# design.net
KiCad netlist of a schematic drawn in Altium Designer
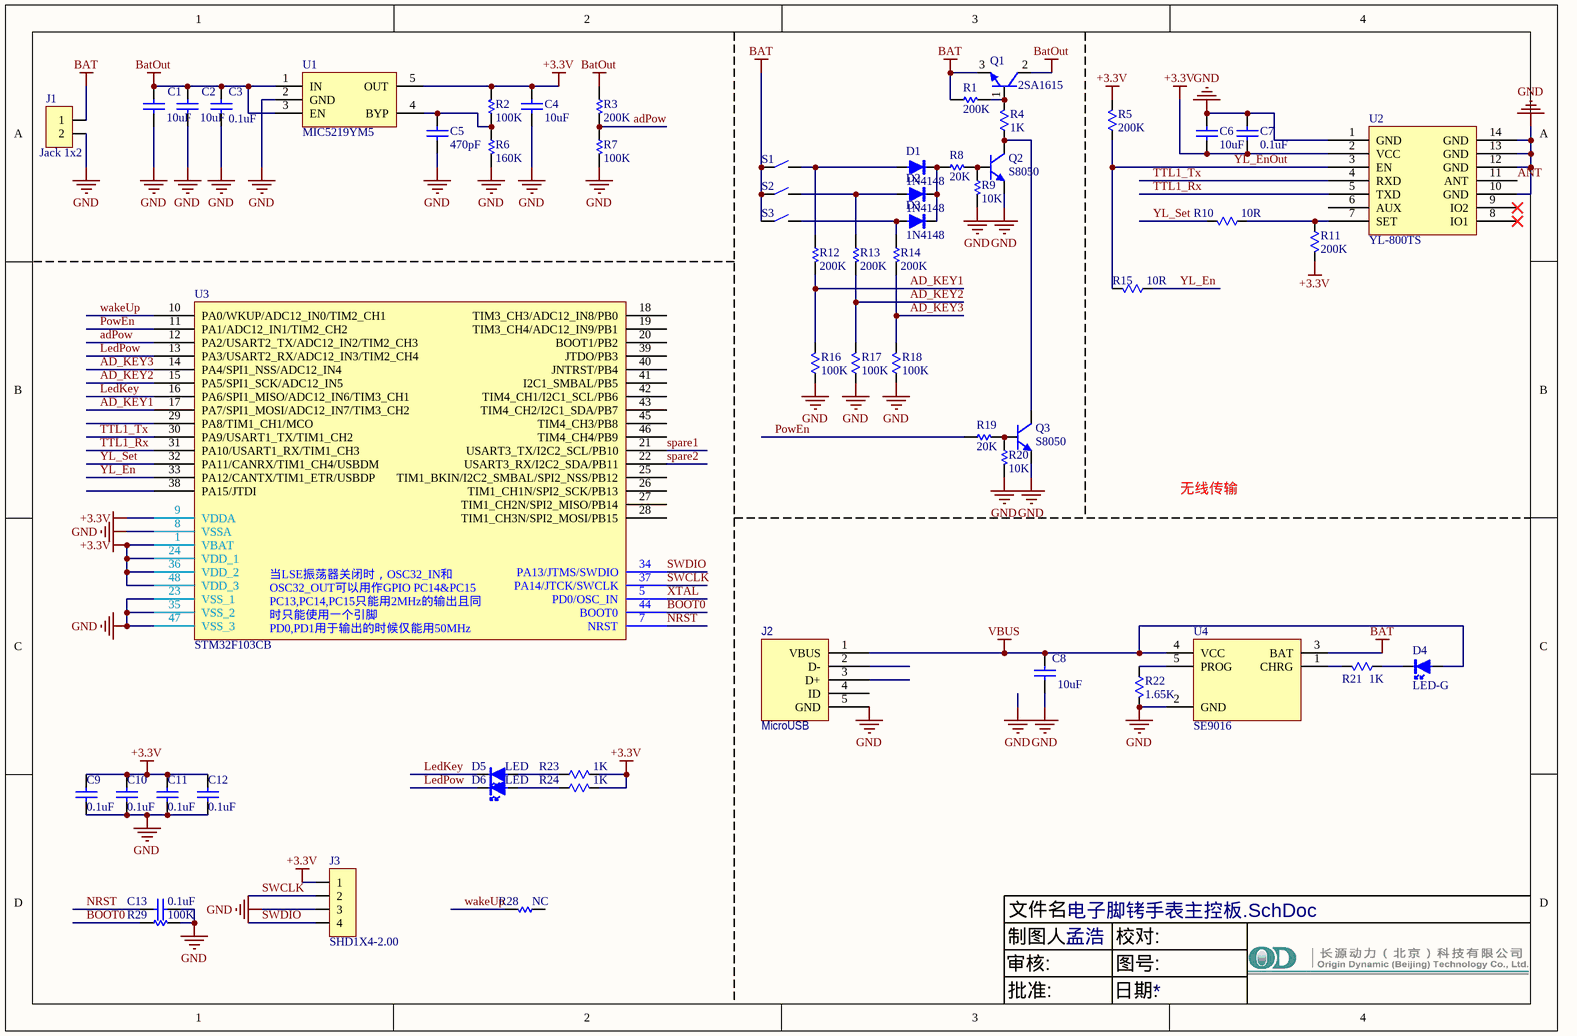
[diagram p0: 电子脚铐手表主控板.SchDoc]

(export (version "E")
  (design (tool "Eeschema 10.0.6"))
  (components
    (comp (ref "C1")
      (value "10uF")
      (footprint "C0603")
      (description "CAP")
      (fields (field (name "PUBLISHER") "Altium Limited"))
      (libsource (lib "Passive Components Class") (part "CAP"))
    )
    (comp (ref "C2")
      (value "10uF")
      (footprint "C0603")
      (description "CAP")
      (fields (field (name "PUBLISHER") "Altium Limited"))
      (libsource (lib "Passive Components Class") (part "CAP"))
    )
    (comp (ref "C3") (value "0.1uF") (footprint "C0603") (libsource (lib "RLCYDF") (part "Cap Semi")))
    (comp (ref "C4")
      (value "10uF")
      (footprint "C0603")
      (description "CAP")
      (fields (field (name "PUBLISHER") "Altium Limited"))
      (libsource (lib "Passive Components Class") (part "CAP"))
    )
    (comp (ref "C5")
      (value "470pF")
      (footprint "C0603")
      (description "CAP")
      (fields (field (name "PUBLISHER") "Altium Limited"))
      (libsource (lib "Passive Components Class") (part "CAP"))
    )
    (comp (ref "C6")
      (value "10uF")
      (footprint "C0603")
      (description "CAP")
      (fields (field (name "PUBLISHER") "Altium Limited"))
      (libsource (lib "Passive Components Class") (part "CAP"))
    )
    (comp (ref "C7")
      (value "0.1uF")
      (footprint "C0603")
      (description "CAP")
      (fields (field (name "PUBLISHER") "Altium Limited"))
      (libsource (lib "Passive Components Class") (part "CAP"))
    )
    (comp (ref "C8")
      (value "10uF")
      (footprint "C0603")
      (description "Capacitor")
      (fields (field (name "Comment") "Cap") (field (name "PUBLISHER") "Altium Limited"))
      (libsource (lib "Miscellaneous Devices") (part "Cap"))
    )
    (comp (ref "C9") (value "0.1uF") (footprint "C0603") (libsource (lib "RLCYDF") (part "Cap Semi")))
    (comp (ref "C10") (value "0.1uF") (footprint "C0603") (libsource (lib "RLCYDF") (part "Cap Semi")))
    (comp (ref "C11") (value "0.1uF") (footprint "C0603") (libsource (lib "RLCYDF") (part "Cap Semi")))
    (comp (ref "C12") (value "0.1uF") (footprint "C0603") (libsource (lib "RLCYDF") (part "Cap Semi")))
    (comp (ref "C13") (value "0.1uF") (footprint "C0603") (libsource (lib "RLCYDF") (part "Cap Semi")))
    (comp (ref "D1")
      (value "1N4148")
      (footprint "SOD-80-S")
      (description "Silicon Epitaxial Planar Diodes")
      (libsource (lib "Passive Components Class") (part "DIODE-SWITCHING"))
    )
    (comp (ref "D2")
      (value "1N4148")
      (footprint "SOD-80-S")
      (description "Silicon Epitaxial Planar Diodes")
      (libsource (lib "Passive Components Class") (part "DIODE-SWITCHING"))
    )
    (comp (ref "D3")
      (value "1N4148")
      (footprint "SOD-80-S")
      (description "Silicon Epitaxial Planar Diodes")
      (libsource (lib "Passive Components Class") (part "DIODE-SWITCHING"))
    )
    (comp (ref "D4")
      (value "LED-G")
      (footprint "LED0805")
      (libsource (lib "Passive Components Class") (part "LED"))
    )
    (comp (ref "D5")
      (value "LED")
      (footprint "LED0805")
      (libsource (lib "Passive Components Class") (part "LED"))
    )
    (comp (ref "D6")
      (value "LED")
      (footprint "LED0805")
      (libsource (lib "Passive Components Class") (part "LED"))
    )
    (comp (ref "J1")
      (value "Jack 1x2")
      (footprint "Jk1*2-2.0")
      (description "插座")
      (libsource (lib "Connector") (part "Jack 1x2"))
    )
    (comp (ref "J2") (value "MicroUSB") (footprint "MICRO-USB") (libsource (lib "JLib") (part "MicroUSB")))
    (comp (ref "J3")
      (value "SHD1X4-2.00")
      (footprint "Jk1*4-2.0")
      (libsource (lib "Connector Class") (part "HEADER1X4"))
    )
    (comp (ref "Q1") (value "2SA1615") (footprint "TO-252") (libsource (lib "ArmArmor") (part "MJD122")))
    (comp (ref "Q2")
      (value "S8050")
      (footprint "SOT-23")
      (description "NPN triode, 0.5A Max")
      (libsource (lib "RLCYDF") (part "S8050"))
    )
    (comp (ref "Q3")
      (value "S8050")
      (footprint "SOT-23")
      (description "NPN triode, 0.5A Max")
      (libsource (lib "RLCYDF") (part "S8050"))
    )
    (comp (ref "R1") (value "200K") (footprint "R0603") (libsource (lib "RLCYDF") (part "Res")))
    (comp (ref "R2") (value "100K") (footprint "R0603") (libsource (lib "RLCYDF") (part "Res")))
    (comp (ref "R3") (value "200K") (footprint "R0603") (libsource (lib "RLCYDF") (part "Res")))
    (comp (ref "R4")
      (value "1K")
      (footprint "R0603")
      (description "Resistor")
      (fields (field (name "PUBLISHER") "Altium Limited"))
      (libsource (lib "Passive Components Class") (part "RES"))
    )
    (comp (ref "R5")
      (value "200K")
      (footprint "R0603")
      (description "Resistor")
      (fields (field (name "PUBLISHER") "Altium Limited"))
      (libsource (lib "Passive Components Class") (part "RES"))
    )
    (comp (ref "R6") (value "160K") (footprint "R0603") (libsource (lib "RLCYDF") (part "Res")))
    (comp (ref "R7") (value "100K") (footprint "R0603") (libsource (lib "RLCYDF") (part "Res")))
    (comp (ref "R8") (value "20K") (footprint "R0603") (libsource (lib "RLCYDF") (part "Res")))
    (comp (ref "R9") (value "10K") (footprint "R0603") (libsource (lib "RLCYDF") (part "Res")))
    (comp (ref "R10")
      (value "10R")
      (footprint "R0603")
      (description "Resistor")
      (fields (field (name "Comment") "200K") (field (name "PUBLISHER") "Altium Limited"))
      (libsource (lib "Passive Components Class") (part "RES"))
    )
    (comp (ref "R11")
      (value "200K")
      (footprint "R0603")
      (description "Resistor")
      (fields (field (name "PUBLISHER") "Altium Limited"))
      (libsource (lib "Passive Components Class") (part "RES"))
    )
    (comp (ref "R12") (value "200K") (footprint "R0603") (libsource (lib "RLCYDF") (part "Res")))
    (comp (ref "R13") (value "200K") (footprint "R0603") (libsource (lib "RLCYDF") (part "Res")))
    (comp (ref "R14") (value "200K") (footprint "R0603") (libsource (lib "RLCYDF") (part "Res")))
    (comp (ref "R15")
      (value "10R")
      (footprint "R0603")
      (description "Resistor")
      (fields (field (name "Comment") "200K") (field (name "PUBLISHER") "Altium Limited"))
      (libsource (lib "Passive Components Class") (part "RES"))
    )
    (comp (ref "R16")
      (value "100K")
      (footprint "R0603")
      (description "Resistor")
      (fields (field (name "PUBLISHER") "Altium Limited"))
      (libsource (lib "Passive Components Class") (part "RES"))
    )
    (comp (ref "R17")
      (value "100K")
      (footprint "R0603")
      (description "Resistor")
      (fields (field (name "PUBLISHER") "Altium Limited"))
      (libsource (lib "Passive Components Class") (part "RES"))
    )
    (comp (ref "R18")
      (value "100K")
      (footprint "R0603")
      (description "Resistor")
      (fields (field (name "PUBLISHER") "Altium Limited"))
      (libsource (lib "Passive Components Class") (part "RES"))
    )
    (comp (ref "R19") (value "20K") (footprint "R0603") (libsource (lib "RLCYDF") (part "Res")))
    (comp (ref "R20") (value "10K") (footprint "R0603") (libsource (lib "RLCYDF") (part "Res")))
    (comp (ref "R21")
      (value "1K")
      (footprint "R0603")
      (description "Resistor")
      (fields (field (name "PUBLISHER") "Altium Limited"))
      (libsource (lib "UP-Robot") (part "Res"))
    )
    (comp (ref "R22")
      (value "1.65K")
      (footprint "R0603")
      (description "Resistor")
      (fields (field (name "PUBLISHER") "Altium Limited"))
      (libsource (lib "Temp") (part "Res"))
    )
    (comp (ref "R23")
      (value "1K")
      (footprint "R0603")
      (description "Resistor")
      (fields (field (name "PUBLISHER") "Altium Limited"))
      (libsource (lib "UP-Robot") (part "Res"))
    )
    (comp (ref "R24")
      (value "1K")
      (footprint "R0603")
      (description "Resistor")
      (fields (field (name "PUBLISHER") "Altium Limited"))
      (libsource (lib "UP-Robot") (part "Res"))
    )
    (comp (ref "R28") (value "NC") (footprint "R0603") (libsource (lib "RLCYDF") (part "Res")))
    (comp (ref "R29") (value "100K") (footprint "R0603") (libsource (lib "RLCYDF") (part "Res")))
    (comp (ref "S1") (value "Switch") (footprint "SW-6X6X8") (libsource (lib "Connector") (part "Sw")))
    (comp (ref "S2") (value "Switch") (footprint "SW-6X6X8") (libsource (lib "Connector") (part "Sw")))
    (comp (ref "S3") (value "Switch") (footprint "SW-6X6X8") (libsource (lib "Connector") (part "Sw")))
    (comp (ref "U1") (value "MIC5219YM5") (footprint "SOT-23-5") (libsource (lib "Power") (part "MIC5205")))
    (comp (ref "U2") (value "YL-800TS") (footprint "YL-800TS") (libsource (lib "Module") (part "YL-800TS")))
    (comp (ref "U3")
      (value "STM32F103CB")
      (footprint "LQFP48")
      (libsource (lib "stm32") (part "STM32F103Cx"))
    )
    (comp (ref "U4") (value "SE9016") (footprint "SOT-23-5") (libsource (lib "chip") (part "SE9016")))
  )
  (nets
    (net (code "1") (name "+3.3V") (class "Default")
      (node (ref "C10") (pin "1") (pinfunction "1_1") (pintype "passive"))
      (node (ref "C11") (pin "1") (pinfunction "1_1") (pintype "passive"))
      (node (ref "C12") (pin "1") (pinfunction "1_1") (pintype "passive"))
      (node (ref "C4") (pin "1") (pinfunction "1_1") (pintype "passive"))
      (node (ref "C6") (pin "1") (pinfunction "1_1") (pintype "passive"))
      (node (ref "C7") (pin "1") (pinfunction "1_1") (pintype "passive"))
      (node (ref "C9") (pin "1") (pinfunction "1_1") (pintype "passive"))
      (node (ref "J3") (pin "1") (pinfunction "1_1") (pintype "passive"))
      (node (ref "R11") (pin "2") (pinfunction "2_2") (pintype "passive"))
      (node (ref "R2") (pin "2") (pinfunction "2_2") (pintype "passive"))
      (node (ref "R23") (pin "1") (pinfunction "1_1") (pintype "passive"))
      (node (ref "R24") (pin "1") (pinfunction "1_1") (pintype "passive"))
      (node (ref "R5") (pin "2") (pinfunction "2_2") (pintype "passive"))
      (node (ref "U1") (pin "5") (pinfunction "OUT_5") (pintype "passive"))
      (node (ref "U2") (pin "2") (pinfunction "VCC_2") (pintype "passive"))
      (node (ref "U3") (pin "1") (pinfunction "VBAT_1") (pintype "power_in"))
      (node (ref "U3") (pin "24") (pinfunction "VDD_1_24") (pintype "power_in"))
      (node (ref "U3") (pin "36") (pinfunction "VDD_2_36") (pintype "power_in"))
      (node (ref "U3") (pin "48") (pinfunction "VDD_3_48") (pintype "power_in"))
      (node (ref "U3") (pin "9") (pinfunction "VDDA_9") (pintype "power_in"))
    )
    (net (code "2") (name "/AD_KEY1") (class "Default")
      (node (ref "R12") (pin "2") (pinfunction "2_2") (pintype "passive"))
      (node (ref "R16") (pin "2") (pinfunction "2_2") (pintype "passive"))
      (node (ref "U3") (pin "17") (pinfunction "PA7/SPI1_MOSI/ADC12_IN7/TIM3_CH2_17") (pintype "passive"))
    )
    (net (code "3") (name "/AD_KEY2") (class "Default")
      (node (ref "R13") (pin "2") (pinfunction "2_2") (pintype "passive"))
      (node (ref "R17") (pin "2") (pinfunction "2_2") (pintype "passive"))
      (node (ref "U3") (pin "15") (pinfunction "PA5/SPI1_SCK/ADC12_IN5_15") (pintype "passive"))
    )
    (net (code "4") (name "/AD_KEY3") (class "Default")
      (node (ref "R14") (pin "2") (pinfunction "2_2") (pintype "passive"))
      (node (ref "R18") (pin "2") (pinfunction "2_2") (pintype "passive"))
      (node (ref "U3") (pin "14") (pinfunction "PA4/SPI1_NSS/ADC12_IN4_14") (pintype "passive"))
    )
    (net (code "5") (name "/ANT") (class "Default")
      (node (ref "U2") (pin "11") (pinfunction "ANT_11") (pintype "passive"))
    )
    (net (code "6") (name "/BOOT0") (class "Default")
      (node (ref "R29") (pin "1") (pinfunction "1_1") (pintype "passive"))
      (node (ref "U3") (pin "44") (pinfunction "BOOT0_44") (pintype "passive"))
    )
    (net (code "7") (name "/LedKey") (class "Default")
      (node (ref "D5") (pin "2") (pinfunction "K_2") (pintype "passive"))
      (node (ref "U3") (pin "16") (pinfunction "PA6/SPI1_MISO/ADC12_IN6/TIM3_CH1_16") (pintype "passive"))
    )
    (net (code "8") (name "/LedPow") (class "Default")
      (node (ref "D6") (pin "2") (pinfunction "K_2") (pintype "passive"))
      (node (ref "U3") (pin "13") (pinfunction "PA3/USART2_RX/ADC12_IN3/TIM2_CH4_13") (pintype "passive"))
    )
    (net (code "9") (name "/NRST") (class "Default")
      (node (ref "C13") (pin "1") (pinfunction "1_1") (pintype "passive"))
      (node (ref "U3") (pin "7") (pinfunction "NRST_7") (pintype "passive"))
    )
    (net (code "10") (name "/PowEn") (class "Default")
      (node (ref "R19") (pin "1") (pinfunction "1_1") (pintype "passive"))
      (node (ref "U3") (pin "11") (pinfunction "PA1/ADC12_IN1/TIM2_CH2_11") (pintype "passive"))
    )
    (net (code "11") (name "/SWCLK") (class "Default")
      (node (ref "J3") (pin "2") (pinfunction "2_2") (pintype "passive"))
      (node (ref "U3") (pin "37") (pinfunction "PA14/JTCK/SWCLK_37") (pintype "passive"))
    )
    (net (code "12") (name "/SWDIO") (class "Default")
      (node (ref "J3") (pin "4") (pinfunction "4_4") (pintype "passive"))
      (node (ref "U3") (pin "34") (pinfunction "PA13/JTMS/SWDIO_34") (pintype "passive"))
    )
    (net (code "13") (name "/TTL1_Rx") (class "Default")
      (node (ref "U2") (pin "5") (pinfunction "TXD_5") (pintype "passive"))
      (node (ref "U3") (pin "31") (pinfunction "PA10/USART1_RX/TIM1_CH3_31") (pintype "passive"))
    )
    (net (code "14") (name "/TTL1_Tx") (class "Default")
      (node (ref "U2") (pin "4") (pinfunction "RXD_4") (pintype "passive"))
      (node (ref "U3") (pin "30") (pinfunction "PA9/USART1_TX/TIM1_CH2_30") (pintype "passive"))
    )
    (net (code "15") (name "/XTAL") (class "Default")
      (node (ref "U3") (pin "5") (pinfunction "PD0/OSC_IN_5") (pintype "passive"))
    )
    (net (code "16") (name "/YL_En") (class "Default")
      (node (ref "R15") (pin "1") (pinfunction "1_1") (pintype "passive"))
      (node (ref "U3") (pin "33") (pinfunction "PA12/CANTX/TIM1_ETR/USBDP_33") (pintype "passive"))
    )
    (net (code "17") (name "/YL_EnOut") (class "Default")
      (node (ref "R15") (pin "2") (pinfunction "2_2") (pintype "passive"))
      (node (ref "R5") (pin "1") (pinfunction "1_1") (pintype "passive"))
      (node (ref "U2") (pin "3") (pinfunction "EN_3") (pintype "passive"))
    )
    (net (code "18") (name "/YL_Set") (class "Default")
      (node (ref "R10") (pin "2") (pinfunction "2_2") (pintype "passive"))
      (node (ref "U3") (pin "32") (pinfunction "PA11/CANRX/TIM1_CH4/USBDM_32") (pintype "passive"))
    )
    (net (code "19") (name "/adPow") (class "Default")
      (node (ref "R3") (pin "2") (pinfunction "2_2") (pintype "passive"))
      (node (ref "R7") (pin "1") (pinfunction "1_1") (pintype "passive"))
      (node (ref "U3") (pin "12") (pinfunction "PA2/USART2_TX/ADC12_IN2/TIM2_CH3_12") (pintype "passive"))
    )
    (net (code "20") (name "/spare1") (class "Default")
      (node (ref "U3") (pin "21") (pinfunction "USART3_TX/I2C2_SCL/PB10_21") (pintype "passive"))
    )
    (net (code "21") (name "/spare2") (class "Default")
      (node (ref "U3") (pin "22") (pinfunction "USART3_RX/I2C2_SDA/PB11_22") (pintype "passive"))
    )
    (net (code "22") (name "/wakeUp") (class "Default")
      (node (ref "R28") (pin "2") (pinfunction "2_2") (pintype "passive"))
      (node (ref "U3") (pin "10") (pinfunction "PA0/WKUP/ADC12_IN0/TIM2_CH1_10") (pintype "passive"))
    )
    (net (code "23") (name "BAT") (class "Default")
      (node (ref "J1") (pin "1") (pinfunction "1_1") (pintype "passive"))
      (node (ref "Q1") (pin "3") (pinfunction "E_3") (pintype "passive"))
      (node (ref "R1") (pin "1") (pinfunction "1_1") (pintype "passive"))
      (node (ref "S1") (pin "1") (pinfunction "1_1") (pintype "passive"))
      (node (ref "S2") (pin "1") (pinfunction "1_1") (pintype "passive"))
      (node (ref "S3") (pin "1") (pinfunction "1_1") (pintype "passive"))
      (node (ref "U4") (pin "3") (pinfunction "BAT_3") (pintype "passive"))
    )
    (net (code "24") (name "BatOut") (class "Default")
      (node (ref "C1") (pin "1") (pinfunction "1_1") (pintype "passive"))
      (node (ref "C2") (pin "1") (pinfunction "1_1") (pintype "passive"))
      (node (ref "C3") (pin "2") (pinfunction "2_2") (pintype "passive"))
      (node (ref "Q1") (pin "2") (pinfunction "C_2") (pintype "passive"))
      (node (ref "R3") (pin "1") (pinfunction "1_1") (pintype "passive"))
      (node (ref "U1") (pin "1") (pinfunction "IN_1") (pintype "passive"))
      (node (ref "U1") (pin "3") (pinfunction "EN_3") (pintype "passive"))
    )
    (net (code "25") (name "GND") (class "Default")
      (node (ref "C1") (pin "2") (pinfunction "2_2") (pintype "passive"))
      (node (ref "C10") (pin "2") (pinfunction "2_2") (pintype "passive"))
      (node (ref "C11") (pin "2") (pinfunction "2_2") (pintype "passive"))
      (node (ref "C12") (pin "2") (pinfunction "2_2") (pintype "passive"))
      (node (ref "C13") (pin "2") (pinfunction "2_2") (pintype "passive"))
      (node (ref "C2") (pin "2") (pinfunction "2_2") (pintype "passive"))
      (node (ref "C3") (pin "1") (pinfunction "1_1") (pintype "passive"))
      (node (ref "C4") (pin "2") (pinfunction "2_2") (pintype "passive"))
      (node (ref "C5") (pin "2") (pinfunction "2_2") (pintype "passive"))
      (node (ref "C6") (pin "2") (pinfunction "2_2") (pintype "passive"))
      (node (ref "C7") (pin "2") (pinfunction "2_2") (pintype "passive"))
      (node (ref "C8") (pin "2") (pinfunction "2_2") (pintype "passive"))
      (node (ref "C9") (pin "2") (pinfunction "2_2") (pintype "passive"))
      (node (ref "J1") (pin "2") (pinfunction "2_2") (pintype "passive"))
      (node (ref "J2") (pin "5") (pinfunction "GND_5") (pintype "passive"))
      (node (ref "J3") (pin "3") (pinfunction "3_3") (pintype "passive"))
      (node (ref "Q2") (pin "2") (pinfunction "e_2") (pintype "passive"))
      (node (ref "Q3") (pin "2") (pinfunction "e_2") (pintype "passive"))
      (node (ref "R16") (pin "1") (pinfunction "1_1") (pintype "passive"))
      (node (ref "R17") (pin "1") (pinfunction "1_1") (pintype "passive"))
      (node (ref "R18") (pin "1") (pinfunction "1_1") (pintype "passive"))
      (node (ref "R20") (pin "2") (pinfunction "2_2") (pintype "passive"))
      (node (ref "R22") (pin "1") (pinfunction "1_1") (pintype "passive"))
      (node (ref "R29") (pin "2") (pinfunction "2_2") (pintype "passive"))
      (node (ref "R6") (pin "2") (pinfunction "2_2") (pintype "passive"))
      (node (ref "R7") (pin "2") (pinfunction "2_2") (pintype "passive"))
      (node (ref "R9") (pin "2") (pinfunction "2_2") (pintype "passive"))
      (node (ref "U1") (pin "2") (pinfunction "GND_2") (pintype "passive"))
      (node (ref "U2") (pin "1") (pinfunction "GND_1") (pintype "passive"))
      (node (ref "U2") (pin "10") (pinfunction "GND_10") (pintype "passive"))
      (node (ref "U2") (pin "12") (pinfunction "GND_12") (pintype "passive"))
      (node (ref "U2") (pin "13") (pinfunction "GND_13") (pintype "passive"))
      (node (ref "U2") (pin "14") (pinfunction "GND_14") (pintype "passive"))
      (node (ref "U3") (pin "23") (pinfunction "VSS_1_23") (pintype "power_in"))
      (node (ref "U3") (pin "35") (pinfunction "VSS_2_35") (pintype "power_in"))
      (node (ref "U3") (pin "47") (pinfunction "VSS_3_47") (pintype "power_in"))
      (node (ref "U3") (pin "8") (pinfunction "VSSA_8") (pintype "power_in"))
      (node (ref "U4") (pin "2") (pinfunction "GND_2") (pintype "passive"))
    )
    (net (code "26") (name "Net-(D1-A)") (class "Default")
      (node (ref "D1") (pin "1") (pinfunction "A_1") (pintype "passive"))
      (node (ref "R12") (pin "1") (pinfunction "1_1") (pintype "passive"))
      (node (ref "S1") (pin "2") (pinfunction "2_2") (pintype "passive"))
    )
    (net (code "27") (name "Net-(D1-K)") (class "Default")
      (node (ref "D1") (pin "2") (pinfunction "K_2") (pintype "passive"))
      (node (ref "D2") (pin "2") (pinfunction "K_2") (pintype "passive"))
      (node (ref "D3") (pin "2") (pinfunction "K_2") (pintype "passive"))
      (node (ref "R8") (pin "1") (pinfunction "1_1") (pintype "passive"))
    )
    (net (code "28") (name "Net-(D2-A)") (class "Default")
      (node (ref "D2") (pin "1") (pinfunction "A_1") (pintype "passive"))
      (node (ref "R13") (pin "1") (pinfunction "1_1") (pintype "passive"))
      (node (ref "S2") (pin "2") (pinfunction "2_2") (pintype "passive"))
    )
    (net (code "29") (name "Net-(D3-A)") (class "Default")
      (node (ref "D3") (pin "1") (pinfunction "A_1") (pintype "passive"))
      (node (ref "R14") (pin "1") (pinfunction "1_1") (pintype "passive"))
      (node (ref "S3") (pin "2") (pinfunction "2_2") (pintype "passive"))
    )
    (net (code "30") (name "Net-(D4-K)") (class "Default")
      (node (ref "D4") (pin "2") (pinfunction "K_2") (pintype "passive"))
      (node (ref "R21") (pin "2") (pinfunction "2_2") (pintype "passive"))
    )
    (net (code "31") (name "Net-(D5-A)") (class "Default")
      (node (ref "D5") (pin "1") (pinfunction "A_1") (pintype "passive"))
      (node (ref "R23") (pin "2") (pinfunction "2_2") (pintype "passive"))
    )
    (net (code "32") (name "Net-(D6-A)") (class "Default")
      (node (ref "D6") (pin "1") (pinfunction "A_1") (pintype "passive"))
      (node (ref "R24") (pin "2") (pinfunction "2_2") (pintype "passive"))
    )
    (net (code "33") (name "Net-(Q1-B)") (class "Default")
      (node (ref "Q1") (pin "1") (pinfunction "B_1") (pintype "passive"))
      (node (ref "R1") (pin "2") (pinfunction "2_2") (pintype "passive"))
      (node (ref "R4") (pin "2") (pinfunction "2_2") (pintype "passive"))
    )
    (net (code "34") (name "Net-(Q2-b)") (class "Default")
      (node (ref "Q2") (pin "1") (pinfunction "b_1") (pintype "passive"))
      (node (ref "R8") (pin "2") (pinfunction "2_2") (pintype "passive"))
      (node (ref "R9") (pin "1") (pinfunction "1_1") (pintype "passive"))
    )
    (net (code "35") (name "Net-(Q2-c)") (class "Default")
      (node (ref "Q2") (pin "3") (pinfunction "c_3") (pintype "passive"))
      (node (ref "Q3") (pin "3") (pinfunction "c_3") (pintype "passive"))
      (node (ref "R4") (pin "1") (pinfunction "1_1") (pintype "passive"))
    )
    (net (code "36") (name "Net-(Q3-b)") (class "Default")
      (node (ref "Q3") (pin "1") (pinfunction "b_1") (pintype "passive"))
      (node (ref "R19") (pin "2") (pinfunction "2_2") (pintype "passive"))
      (node (ref "R20") (pin "1") (pinfunction "1_1") (pintype "passive"))
    )
    (net (code "37") (name "Net-(U1-BYP)") (class "Default")
      (node (ref "C5") (pin "1") (pinfunction "1_1") (pintype "passive"))
      (node (ref "R2") (pin "1") (pinfunction "1_1") (pintype "passive"))
      (node (ref "R6") (pin "1") (pinfunction "1_1") (pintype "passive"))
      (node (ref "U1") (pin "4") (pinfunction "BYP_4") (pintype "passive"))
    )
    (net (code "38") (name "Net-(U2-SET)") (class "Default")
      (node (ref "R10") (pin "1") (pinfunction "1_1") (pintype "passive"))
      (node (ref "R11") (pin "1") (pinfunction "1_1") (pintype "passive"))
      (node (ref "U2") (pin "7") (pinfunction "SET_7") (pintype "passive"))
    )
    (net (code "39") (name "Net-(U4-CHRG)") (class "Default")
      (node (ref "R21") (pin "1") (pinfunction "1_1") (pintype "passive"))
      (node (ref "U4") (pin "1") (pinfunction "CHRG_1") (pintype "passive"))
    )
    (net (code "40") (name "Net-(U4-PROG)") (class "Default")
      (node (ref "R22") (pin "2") (pinfunction "2_2") (pintype "passive"))
      (node (ref "U4") (pin "5") (pinfunction "PROG_5") (pintype "passive"))
    )
    (net (code "41") (name "VBUS") (class "Default")
      (node (ref "C8") (pin "1") (pinfunction "1_1") (pintype "passive"))
      (node (ref "D4") (pin "1") (pinfunction "A_1") (pintype "passive"))
      (node (ref "J2") (pin "1") (pinfunction "VBUS_1") (pintype "passive"))
      (node (ref "U4") (pin "4") (pinfunction "VCC_4") (pintype "passive"))
    )
    (net (code "42") (name "unconnected-(J2-D+-Pad3)") (class "Default")
      (node (ref "J2") (pin "3") (pinfunction "D+_3") (pintype "passive"))
    )
    (net (code "43") (name "unconnected-(J2-D--Pad2)") (class "Default")
      (node (ref "J2") (pin "2") (pinfunction "D-_2") (pintype "passive"))
    )
    (net (code "44") (name "unconnected-(J2-ID-Pad4)") (class "Default")
      (node (ref "J2") (pin "4") (pinfunction "ID_4") (pintype "passive"))
    )
    (net (code "45") (name "unconnected-(R28-Pad1)") (class "Default")
      (node (ref "R28") (pin "1") (pinfunction "1_1") (pintype "passive"))
    )
    (net (code "46") (name "unconnected-(U2-AUX-Pad6)") (class "Default")
      (node (ref "U2") (pin "6") (pinfunction "AUX_6") (pintype "passive"))
    )
    (net (code "47") (name "unconnected-(U2-IO1-Pad8)") (class "Default")
      (node (ref "U2") (pin "8") (pinfunction "IO1_8") (pintype "passive+no_connect"))
    )
    (net (code "48") (name "unconnected-(U2-IO2-Pad9)") (class "Default")
      (node (ref "U2") (pin "9") (pinfunction "IO2_9") (pintype "passive+no_connect"))
    )
    (net (code "49") (name "unconnected-(U3-BOOT1{slash}PB2-Pad20)") (class "Default")
      (node (ref "U3") (pin "20") (pinfunction "BOOT1/PB2_20") (pintype "passive"))
    )
    (net (code "50") (name "unconnected-(U3-I2C1_SMBAL{slash}PB5-Pad41)") (class "Default")
      (node (ref "U3") (pin "41") (pinfunction "I2C1_SMBAL/PB5_41") (pintype "passive"))
    )
    (net (code "51") (name "unconnected-(U3-JNTRST{slash}PB4-Pad40)") (class "Default")
      (node (ref "U3") (pin "40") (pinfunction "JNTRST/PB4_40") (pintype "passive"))
    )
    (net (code "52") (name "unconnected-(U3-JTDO{slash}PB3-Pad39)") (class "Default")
      (node (ref "U3") (pin "39") (pinfunction "JTDO/PB3_39") (pintype "passive"))
    )
    (net (code "53") (name "unconnected-(U3-PA8{slash}TIM1_CH1{slash}MCO-Pad29)") (class "Default")
      (node (ref "U3") (pin "29") (pinfunction "PA8/TIM1_CH1/MCO_29") (pintype "passive"))
    )
    (net (code "54") (name "unconnected-(U3-PA15{slash}JTDI-Pad38)") (class "Default")
      (node (ref "U3") (pin "38") (pinfunction "PA15/JTDI_38") (pintype "passive"))
    )
    (net (code "55") (name "unconnected-(U3-PC13-TAMPER-RTC-Pad2)") (class "Default")
      (node (ref "U3") (pin "2") (pinfunction "PC13-TAMPER-RTC_2") (pintype "passive"))
    )
    (net (code "56") (name "unconnected-(U3-PC14-OSC32_IN-Pad3)") (class "Default")
      (node (ref "U3") (pin "3") (pinfunction "PC14-OSC32_IN_3") (pintype "passive"))
    )
    (net (code "57") (name "unconnected-(U3-PC15-OSC32_OUT-Pad4)") (class "Default")
      (node (ref "U3") (pin "4") (pinfunction "PC15-OSC32_OUT_4") (pintype "passive"))
    )
    (net (code "58") (name "unconnected-(U3-PD1{slash}OSC_OUT-Pad6)") (class "Default")
      (node (ref "U3") (pin "6") (pinfunction "PD1/OSC_OUT_6") (pintype "passive"))
    )
    (net (code "59") (name "unconnected-(U3-TIM1_BKIN{slash}I2C2_SMBAL{slash}SPI2_NSS{slash}PB12-Pad25)") (class "Default")
      (node (ref "U3") (pin "25") (pinfunction "TIM1_BKIN/I2C2_SMBAL/SPI2_NSS/PB12_25") (pintype "passive"))
    )
    (net (code "60") (name "unconnected-(U3-TIM1_CH1N{slash}SPI2_SCK{slash}PB13-Pad26)") (class "Default")
      (node (ref "U3") (pin "26") (pinfunction "TIM1_CH1N/SPI2_SCK/PB13_26") (pintype "passive"))
    )
    (net (code "61") (name "unconnected-(U3-TIM1_CH2N{slash}SPI2_MISO{slash}PB14-Pad27)") (class "Default")
      (node (ref "U3") (pin "27") (pinfunction "TIM1_CH2N/SPI2_MISO/PB14_27") (pintype "passive"))
    )
    (net (code "62") (name "unconnected-(U3-TIM1_CH3N{slash}SPI2_MOSI{slash}PB15-Pad28)") (class "Default")
      (node (ref "U3") (pin "28") (pinfunction "TIM1_CH3N/SPI2_MOSI/PB15_28") (pintype "passive"))
    )
    (net (code "63") (name "unconnected-(U3-TIM3_CH3{slash}ADC12_IN8{slash}PB0-Pad18)") (class "Default")
      (node (ref "U3") (pin "18") (pinfunction "TIM3_CH3/ADC12_IN8/PB0_18") (pintype "passive"))
    )
    (net (code "64") (name "unconnected-(U3-TIM3_CH4{slash}ADC12_IN9{slash}PB1-Pad19)") (class "Default")
      (node (ref "U3") (pin "19") (pinfunction "TIM3_CH4/ADC12_IN9/PB1_19") (pintype "passive"))
    )
    (net (code "65") (name "unconnected-(U3-TIM4_CH1{slash}I2C1_SCL{slash}PB6-Pad42)") (class "Default")
      (node (ref "U3") (pin "42") (pinfunction "TIM4_CH1/I2C1_SCL/PB6_42") (pintype "passive"))
    )
    (net (code "66") (name "unconnected-(U3-TIM4_CH2{slash}I2C1_SDA{slash}PB7-Pad43)") (class "Default")
      (node (ref "U3") (pin "43") (pinfunction "TIM4_CH2/I2C1_SDA/PB7_43") (pintype "passive"))
    )
    (net (code "67") (name "unconnected-(U3-TIM4_CH3{slash}PB8-Pad45)") (class "Default")
      (node (ref "U3") (pin "45") (pinfunction "TIM4_CH3/PB8_45") (pintype "passive"))
    )
    (net (code "68") (name "unconnected-(U3-TIM4_CH4{slash}PB9-Pad46)") (class "Default")
      (node (ref "U3") (pin "46") (pinfunction "TIM4_CH4/PB9_46") (pintype "passive"))
    )
  )
)
